# FFT_IFFT.net
KiCad netlist of a schematic drawn in Altium Designer
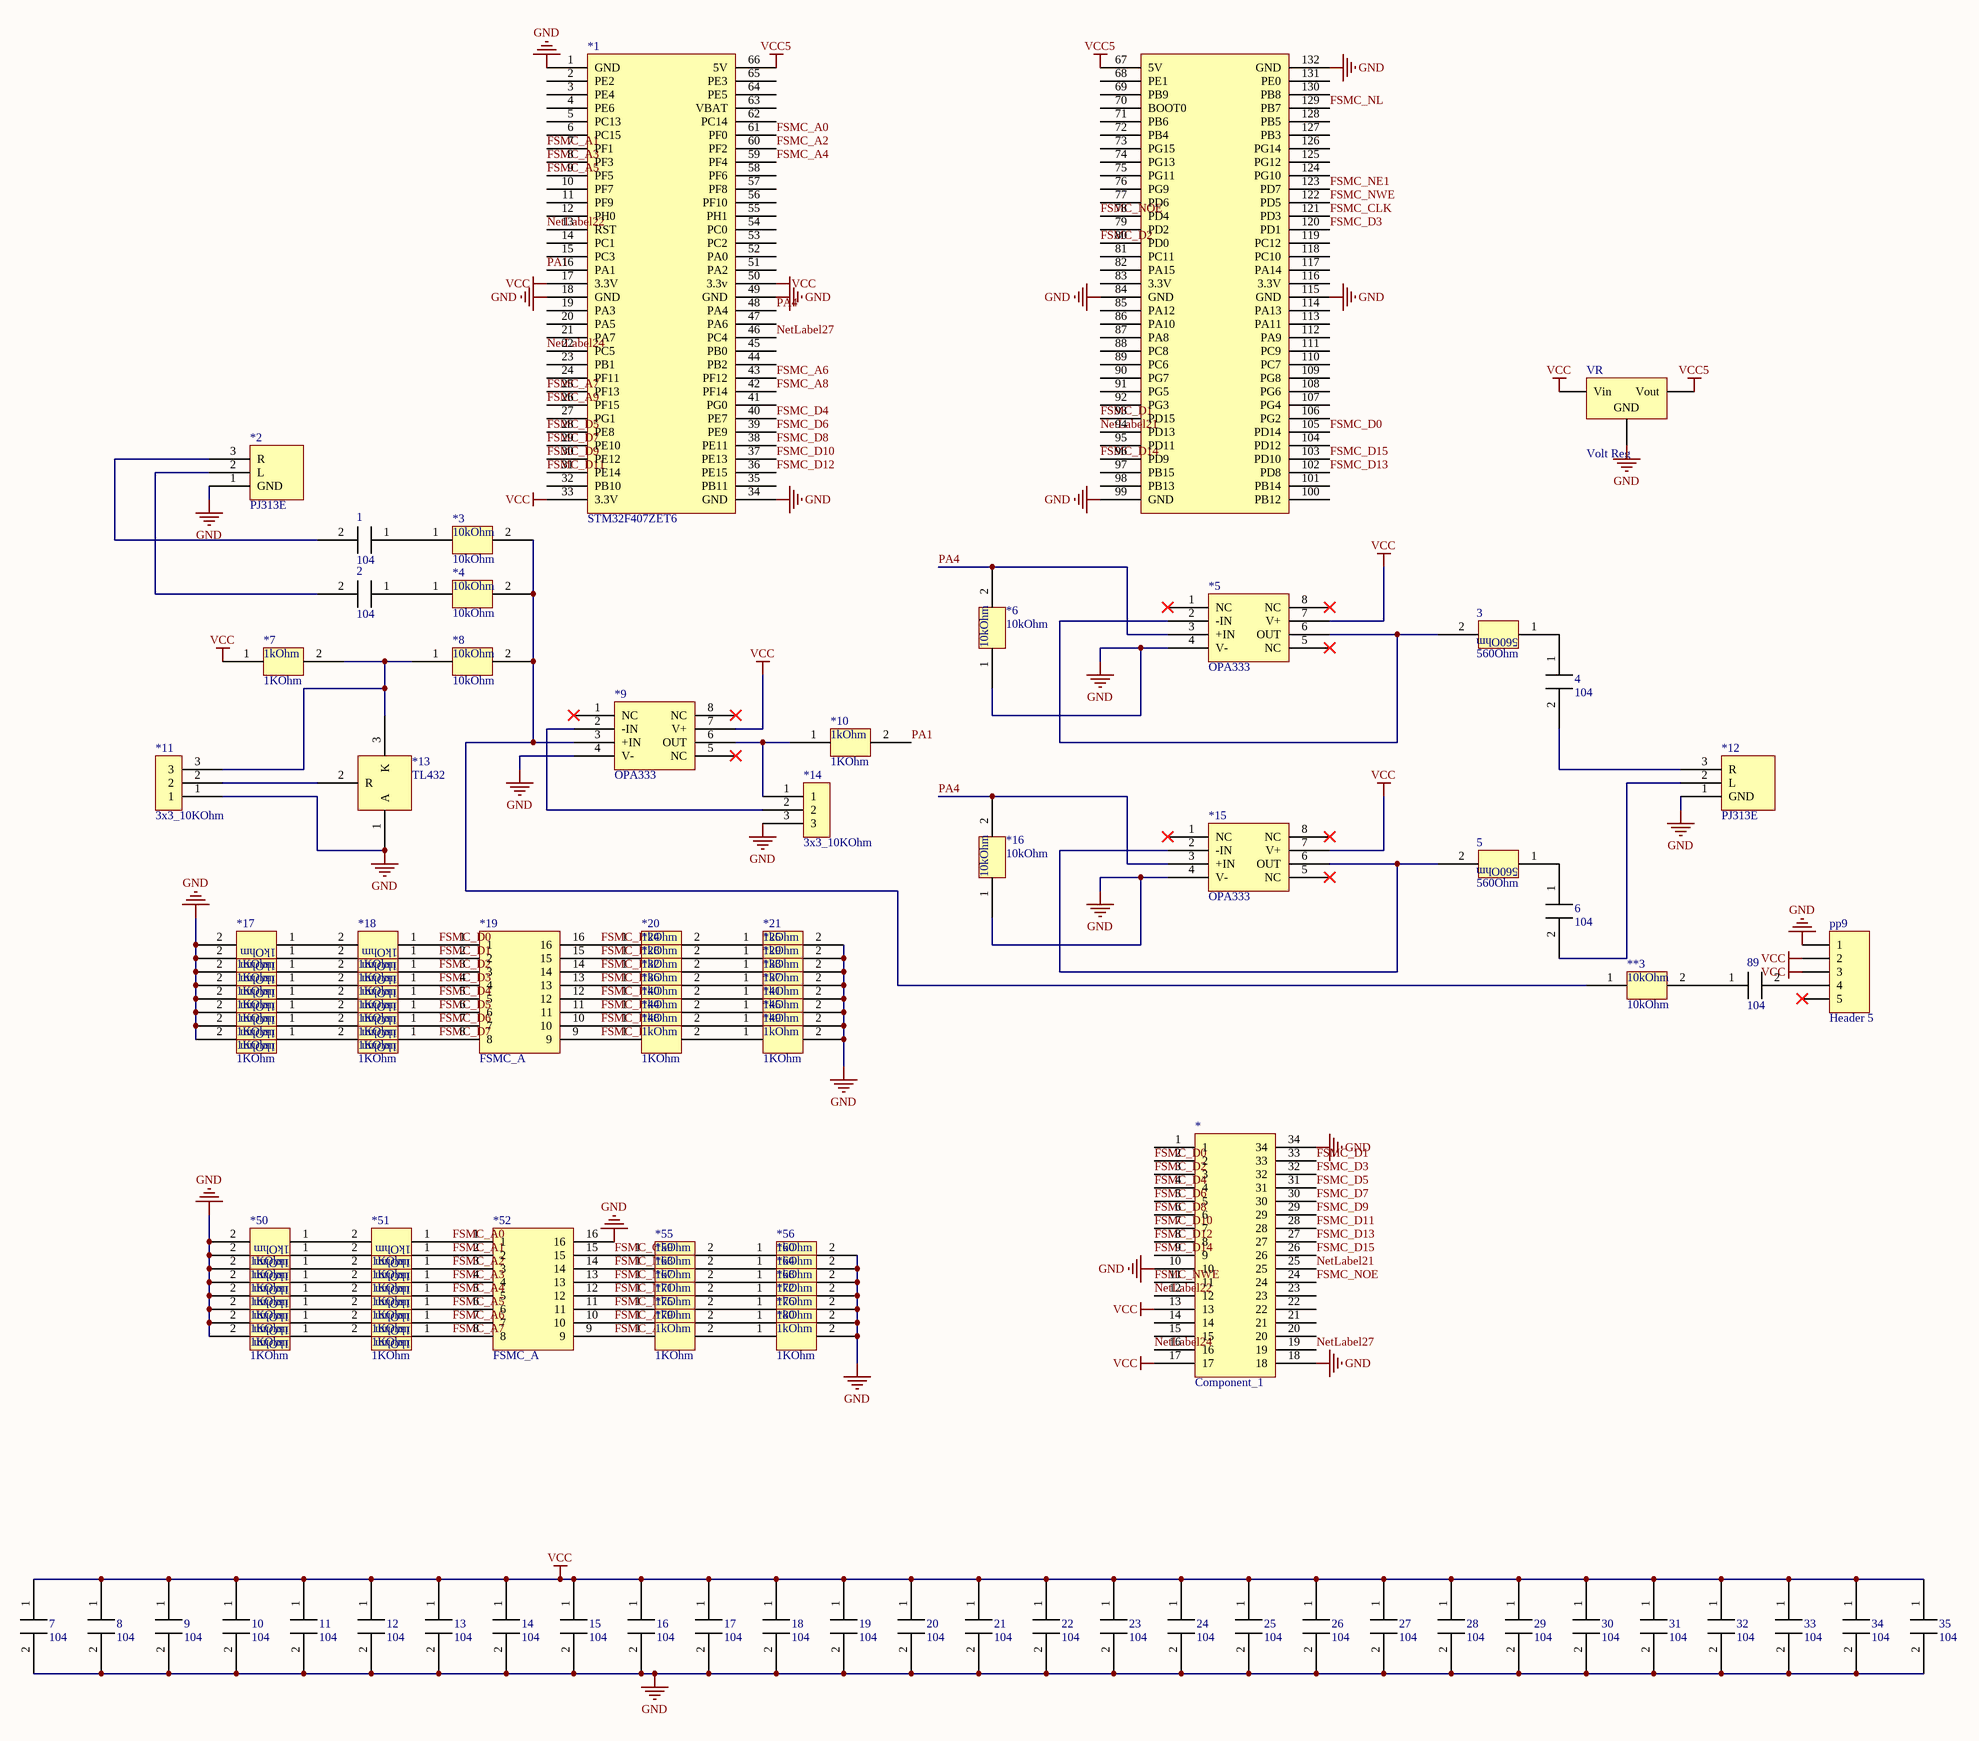
[diagram p0: FFT_IFFT.SchDoc]

(export (version "E")
  (design (tool "Eeschema 10.0.6"))
  (components
    (comp (ref "*")
      (value "Component_1")
      (footprint "PCBComponent_1")
      (libsource (lib "Schlib1") (part "Component_1"))
    )
    (comp (ref "**3") (value "10kOhm") (footprint "104") (libsource (lib "Schlib1") (part "10kOhm")))
    (comp (ref "*1")
      (value "STM32F407ZET6")
      (footprint "STM32F407ZET6")
      (libsource (lib "Schlib1") (part "STM32F407ZET6"))
    )
    (comp (ref "*2") (value "PJ313E") (footprint "PJ313E") (libsource (lib "Schlib1") (part "PJ313E")))
    (comp (ref "*3") (value "10kOhm") (footprint "104") (libsource (lib "Schlib1") (part "10kOhm")))
    (comp (ref "*4") (value "10kOhm") (footprint "104") (libsource (lib "Schlib1") (part "10kOhm")))
    (comp (ref "*5") (value "OPA333") (footprint "OPA333") (libsource (lib "Schlib1") (part "OPA333")))
    (comp (ref "*6") (value "10kOhm") (footprint "104") (libsource (lib "") (part "10kOhm_1")))
    (comp (ref "*7") (value "1KOhm") (footprint "104") (libsource (lib "") (part "1KOhm_1")))
    (comp (ref "*8") (value "10kOhm") (footprint "104") (libsource (lib "Schlib1") (part "10kOhm")))
    (comp (ref "*9") (value "OPA333") (footprint "OPA333") (libsource (lib "Schlib1") (part "OPA333")))
    (comp (ref "*10") (value "1KOhm") (footprint "104") (libsource (lib "") (part "1KOhm_1")))
    (comp (ref "*11")
      (value "3x3_10KOhm")
      (footprint "3x3_10KOhm")
      (libsource (lib "Schlib1") (part "3x3_10KOhm"))
    )
    (comp (ref "*12") (value "PJ313E") (footprint "PJ313E") (libsource (lib "Schlib1") (part "PJ313E")))
    (comp (ref "*13") (value "TL432") (footprint "AO3401") (libsource (lib "Schlib1") (part "TL432")))
    (comp (ref "*14")
      (value "3x3_10KOhm")
      (footprint "3x3_10KOhm")
      (libsource (lib "") (part "3x3_10KOhm_1"))
    )
    (comp (ref "*15") (value "OPA333") (footprint "OPA333") (libsource (lib "Schlib1") (part "OPA333")))
    (comp (ref "*16") (value "10kOhm") (footprint "104") (libsource (lib "") (part "10kOhm_1")))
    (comp (ref "*17") (value "1KOhm") (footprint "104") (libsource (lib "Schlib1") (part "1KOhm")))
    (comp (ref "*18") (value "1KOhm") (footprint "104") (libsource (lib "Schlib1") (part "1KOhm")))
    (comp (ref "*19") (value "FSMC_A") (footprint "DIP32") (libsource (lib "Schlib1") (part "FSMC_A")))
    (comp (ref "*20") (value "1KOhm") (footprint "104") (libsource (lib "") (part "1KOhm_1")))
    (comp (ref "*21") (value "1KOhm") (footprint "104") (libsource (lib "") (part "1KOhm_1")))
    (comp (ref "*22") (value "1KOhm") (footprint "104") (libsource (lib "Schlib1") (part "1KOhm")))
    (comp (ref "*23") (value "1KOhm") (footprint "104") (libsource (lib "Schlib1") (part "1KOhm")))
    (comp (ref "*24") (value "1KOhm") (footprint "104") (libsource (lib "") (part "1KOhm_1")))
    (comp (ref "*25") (value "1KOhm") (footprint "104") (libsource (lib "") (part "1KOhm_1")))
    (comp (ref "*26") (value "1KOhm") (footprint "104") (libsource (lib "Schlib1") (part "1KOhm")))
    (comp (ref "*27") (value "1KOhm") (footprint "104") (libsource (lib "Schlib1") (part "1KOhm")))
    (comp (ref "*28") (value "1KOhm") (footprint "104") (libsource (lib "") (part "1KOhm_1")))
    (comp (ref "*29") (value "1KOhm") (footprint "104") (libsource (lib "") (part "1KOhm_1")))
    (comp (ref "*30") (value "1KOhm") (footprint "104") (libsource (lib "Schlib1") (part "1KOhm")))
    (comp (ref "*31") (value "1KOhm") (footprint "104") (libsource (lib "Schlib1") (part "1KOhm")))
    (comp (ref "*32") (value "1KOhm") (footprint "104") (libsource (lib "") (part "1KOhm_1")))
    (comp (ref "*33") (value "1KOhm") (footprint "104") (libsource (lib "") (part "1KOhm_1")))
    (comp (ref "*34") (value "1KOhm") (footprint "104") (libsource (lib "Schlib1") (part "1KOhm")))
    (comp (ref "*35") (value "1KOhm") (footprint "104") (libsource (lib "Schlib1") (part "1KOhm")))
    (comp (ref "*36") (value "1KOhm") (footprint "104") (libsource (lib "") (part "1KOhm_1")))
    (comp (ref "*37") (value "1KOhm") (footprint "104") (libsource (lib "") (part "1KOhm_1")))
    (comp (ref "*38") (value "1KOhm") (footprint "104") (libsource (lib "Schlib1") (part "1KOhm")))
    (comp (ref "*39") (value "1KOhm") (footprint "104") (libsource (lib "Schlib1") (part "1KOhm")))
    (comp (ref "*40") (value "1KOhm") (footprint "104") (libsource (lib "") (part "1KOhm_1")))
    (comp (ref "*41") (value "1KOhm") (footprint "104") (libsource (lib "") (part "1KOhm_1")))
    (comp (ref "*42") (value "1KOhm") (footprint "104") (libsource (lib "Schlib1") (part "1KOhm")))
    (comp (ref "*43") (value "1KOhm") (footprint "104") (libsource (lib "Schlib1") (part "1KOhm")))
    (comp (ref "*44") (value "1KOhm") (footprint "104") (libsource (lib "") (part "1KOhm_1")))
    (comp (ref "*45") (value "1KOhm") (footprint "104") (libsource (lib "") (part "1KOhm_1")))
    (comp (ref "*46") (value "1KOhm") (footprint "104") (libsource (lib "Schlib1") (part "1KOhm")))
    (comp (ref "*47") (value "1KOhm") (footprint "104") (libsource (lib "Schlib1") (part "1KOhm")))
    (comp (ref "*48") (value "1KOhm") (footprint "104") (libsource (lib "") (part "1KOhm_1")))
    (comp (ref "*49") (value "1KOhm") (footprint "104") (libsource (lib "") (part "1KOhm_1")))
    (comp (ref "*50") (value "1KOhm") (footprint "104") (libsource (lib "Schlib1") (part "1KOhm")))
    (comp (ref "*51") (value "1KOhm") (footprint "104") (libsource (lib "Schlib1") (part "1KOhm")))
    (comp (ref "*52") (value "FSMC_A") (footprint "DIP32") (libsource (lib "Schlib1") (part "FSMC_A")))
    (comp (ref "*53") (value "1KOhm") (footprint "104") (libsource (lib "Schlib1") (part "1KOhm")))
    (comp (ref "*54") (value "1KOhm") (footprint "104") (libsource (lib "Schlib1") (part "1KOhm")))
    (comp (ref "*55") (value "1KOhm") (footprint "104") (libsource (lib "") (part "1KOhm_1")))
    (comp (ref "*56") (value "1KOhm") (footprint "104") (libsource (lib "") (part "1KOhm_1")))
    (comp (ref "*57") (value "1KOhm") (footprint "104") (libsource (lib "Schlib1") (part "1KOhm")))
    (comp (ref "*58") (value "1KOhm") (footprint "104") (libsource (lib "Schlib1") (part "1KOhm")))
    (comp (ref "*59") (value "1KOhm") (footprint "104") (libsource (lib "") (part "1KOhm_1")))
    (comp (ref "*60") (value "1KOhm") (footprint "104") (libsource (lib "") (part "1KOhm_1")))
    (comp (ref "*61") (value "1KOhm") (footprint "104") (libsource (lib "Schlib1") (part "1KOhm")))
    (comp (ref "*62") (value "1KOhm") (footprint "104") (libsource (lib "Schlib1") (part "1KOhm")))
    (comp (ref "*63") (value "1KOhm") (footprint "104") (libsource (lib "") (part "1KOhm_1")))
    (comp (ref "*64") (value "1KOhm") (footprint "104") (libsource (lib "") (part "1KOhm_1")))
    (comp (ref "*65") (value "1KOhm") (footprint "104") (libsource (lib "Schlib1") (part "1KOhm")))
    (comp (ref "*66") (value "1KOhm") (footprint "104") (libsource (lib "Schlib1") (part "1KOhm")))
    (comp (ref "*67") (value "1KOhm") (footprint "104") (libsource (lib "") (part "1KOhm_1")))
    (comp (ref "*68") (value "1KOhm") (footprint "104") (libsource (lib "") (part "1KOhm_1")))
    (comp (ref "*69") (value "1KOhm") (footprint "104") (libsource (lib "Schlib1") (part "1KOhm")))
    (comp (ref "*70") (value "1KOhm") (footprint "104") (libsource (lib "Schlib1") (part "1KOhm")))
    (comp (ref "*71") (value "1KOhm") (footprint "104") (libsource (lib "") (part "1KOhm_1")))
    (comp (ref "*72") (value "1KOhm") (footprint "104") (libsource (lib "") (part "1KOhm_1")))
    (comp (ref "*73") (value "1KOhm") (footprint "104") (libsource (lib "Schlib1") (part "1KOhm")))
    (comp (ref "*74") (value "1KOhm") (footprint "104") (libsource (lib "Schlib1") (part "1KOhm")))
    (comp (ref "*75") (value "1KOhm") (footprint "104") (libsource (lib "") (part "1KOhm_1")))
    (comp (ref "*76") (value "1KOhm") (footprint "104") (libsource (lib "") (part "1KOhm_1")))
    (comp (ref "*77") (value "1KOhm") (footprint "104") (libsource (lib "Schlib1") (part "1KOhm")))
    (comp (ref "*78") (value "1KOhm") (footprint "104") (libsource (lib "Schlib1") (part "1KOhm")))
    (comp (ref "*79") (value "1KOhm") (footprint "104") (libsource (lib "") (part "1KOhm_1")))
    (comp (ref "*80") (value "1KOhm") (footprint "104") (libsource (lib "") (part "1KOhm_1")))
    (comp (ref "1") (value "104") (footprint "104") (libsource (lib "Schlib1") (part "104")))
    (comp (ref "2") (value "104") (footprint "104") (libsource (lib "Schlib1") (part "104")))
    (comp (ref "3") (value "560Ohm") (footprint "104") (libsource (lib "Schlib1") (part "560Ohm")))
    (comp (ref "4") (value "104") (footprint "104") (libsource (lib "Schlib1") (part "104")))
    (comp (ref "5") (value "560Ohm") (footprint "104") (libsource (lib "Schlib1") (part "560Ohm")))
    (comp (ref "6") (value "104") (footprint "104") (libsource (lib "Schlib1") (part "104")))
    (comp (ref "7") (value "104") (footprint "104") (libsource (lib "Schlib1") (part "104")))
    (comp (ref "8") (value "104") (footprint "104") (libsource (lib "Schlib1") (part "104")))
    (comp (ref "9") (value "104") (footprint "104") (libsource (lib "Schlib1") (part "104")))
    (comp (ref "10") (value "104") (footprint "104") (libsource (lib "Schlib1") (part "104")))
    (comp (ref "11") (value "104") (footprint "104") (libsource (lib "Schlib1") (part "104")))
    (comp (ref "12") (value "104") (footprint "104") (libsource (lib "Schlib1") (part "104")))
    (comp (ref "13") (value "104") (footprint "104") (libsource (lib "Schlib1") (part "104")))
    (comp (ref "14") (value "104") (footprint "104") (libsource (lib "Schlib1") (part "104")))
    (comp (ref "15") (value "104") (footprint "104") (libsource (lib "Schlib1") (part "104")))
    (comp (ref "16") (value "104") (footprint "104") (libsource (lib "Schlib1") (part "104")))
    (comp (ref "17") (value "104") (footprint "104") (libsource (lib "Schlib1") (part "104")))
    (comp (ref "18") (value "104") (footprint "104") (libsource (lib "Schlib1") (part "104")))
    (comp (ref "19") (value "104") (footprint "104") (libsource (lib "Schlib1") (part "104")))
    (comp (ref "20") (value "104") (footprint "104") (libsource (lib "Schlib1") (part "104")))
    (comp (ref "21") (value "104") (footprint "104") (libsource (lib "Schlib1") (part "104")))
    (comp (ref "22") (value "104") (footprint "104") (libsource (lib "Schlib1") (part "104")))
    (comp (ref "23") (value "104") (footprint "104") (libsource (lib "Schlib1") (part "104")))
    (comp (ref "24") (value "104") (footprint "104") (libsource (lib "Schlib1") (part "104")))
    (comp (ref "25") (value "104") (footprint "104") (libsource (lib "Schlib1") (part "104")))
    (comp (ref "26") (value "104") (footprint "104") (libsource (lib "Schlib1") (part "104")))
    (comp (ref "27") (value "104") (footprint "104") (libsource (lib "Schlib1") (part "104")))
    (comp (ref "28") (value "104") (footprint "104") (libsource (lib "Schlib1") (part "104")))
    (comp (ref "29") (value "104") (footprint "104") (libsource (lib "Schlib1") (part "104")))
    (comp (ref "30") (value "104") (footprint "104") (libsource (lib "Schlib1") (part "104")))
    (comp (ref "31") (value "104") (footprint "104") (libsource (lib "Schlib1") (part "104")))
    (comp (ref "32") (value "104") (footprint "104") (libsource (lib "Schlib1") (part "104")))
    (comp (ref "33") (value "104") (footprint "104") (libsource (lib "Schlib1") (part "104")))
    (comp (ref "34") (value "104") (footprint "104") (libsource (lib "Schlib1") (part "104")))
    (comp (ref "35") (value "104") (footprint "104") (libsource (lib "Schlib1") (part "104")))
    (comp (ref "89") (value "104") (footprint "104") (libsource (lib "Schlib1") (part "104")))
    (comp (ref "pp9")
      (value "Header 5")
      (footprint "HDR1X5")
      (description "Header, 5-Pin")
      (fields (field (name "PUBLISHER") "Altium Limited"))
      (libsource (lib "Miscellaneous Connectors") (part "Header 5"))
    )
    (comp (ref "VR")
      (value "Volt Reg")
      (footprint "TO252")
      (description "Voltage Regulator")
      (fields (field (name "PUBLISHER") "Altium Limited"))
      (libsource (lib "Miscellaneous Devices") (part "Volt Reg"))
    )
  )
  (nets
    (net (code "1") (name "/FSMC_A0") (class "Default")
      (node (ref "*1") (pin "61") (pinfunction "PF0_61") (pintype "passive"))
      (node (ref "*51") (pin "1") (pintype "passive"))
      (node (ref "*52") (pin "1") (pinfunction "1_1") (pintype "passive"))
    )
    (net (code "2") (name "/FSMC_A1") (class "Default")
      (node (ref "*1") (pin "7") (pinfunction "PF1_7") (pintype "passive"))
      (node (ref "*52") (pin "2") (pinfunction "2_2") (pintype "passive"))
      (node (ref "*54") (pin "1") (pintype "passive"))
    )
    (net (code "3") (name "/FSMC_A2") (class "Default")
      (node (ref "*1") (pin "60") (pinfunction "PF2_60") (pintype "passive"))
      (node (ref "*52") (pin "3") (pinfunction "3_3") (pintype "passive"))
      (node (ref "*58") (pin "1") (pintype "passive"))
    )
    (net (code "4") (name "/FSMC_A3") (class "Default")
      (node (ref "*1") (pin "8") (pinfunction "PF3_8") (pintype "passive"))
      (node (ref "*52") (pin "4") (pinfunction "4_4") (pintype "passive"))
      (node (ref "*62") (pin "1") (pintype "passive"))
    )
    (net (code "5") (name "/FSMC_A4") (class "Default")
      (node (ref "*1") (pin "59") (pinfunction "PF4_59") (pintype "passive"))
      (node (ref "*52") (pin "5") (pinfunction "5_5") (pintype "passive"))
      (node (ref "*66") (pin "1") (pintype "passive"))
    )
    (net (code "6") (name "/FSMC_A5") (class "Default")
      (node (ref "*1") (pin "9") (pinfunction "PF5_9") (pintype "passive"))
      (node (ref "*52") (pin "6") (pinfunction "6_6") (pintype "passive"))
      (node (ref "*70") (pin "1") (pintype "passive"))
    )
    (net (code "7") (name "/FSMC_A6") (class "Default")
      (node (ref "*1") (pin "43") (pinfunction "PF12_43") (pintype "passive"))
      (node (ref "*52") (pin "7") (pinfunction "7_7") (pintype "passive"))
      (node (ref "*74") (pin "1") (pintype "passive"))
    )
    (net (code "8") (name "/FSMC_A7") (class "Default")
      (node (ref "*1") (pin "25") (pinfunction "PF13_25") (pintype "passive"))
      (node (ref "*52") (pin "8") (pinfunction "8_8") (pintype "passive"))
      (node (ref "*78") (pin "1") (pintype "passive"))
    )
    (net (code "9") (name "/FSMC_A8") (class "Default")
      (node (ref "*1") (pin "42") (pinfunction "PF14_42") (pintype "passive"))
      (node (ref "*52") (pin "9") (pinfunction "9_9") (pintype "passive"))
      (node (ref "*79") (pin "1") (pintype "passive"))
    )
    (net (code "10") (name "/FSMC_A9") (class "Default")
      (node (ref "*1") (pin "26") (pinfunction "PF15_26") (pintype "passive"))
      (node (ref "*52") (pin "10") (pinfunction "10_10") (pintype "passive"))
      (node (ref "*75") (pin "1") (pintype "passive"))
    )
    (net (code "11") (name "/FSMC_CLK") (class "Default")
      (node (ref "*1") (pin "121") (pinfunction "PD3_121") (pintype "passive"))
      (node (ref "*52") (pin "15") (pinfunction "15_15") (pintype "passive"))
      (node (ref "*55") (pin "1") (pintype "passive"))
    )
    (net (code "12") (name "/FSMC_D0") (class "Default")
      (node (ref "*") (pin "2") (pinfunction "2_2") (pintype "passive"))
      (node (ref "*1") (pin "105") (pinfunction "PD14_105") (pintype "passive"))
      (node (ref "*18") (pin "1") (pintype "passive"))
      (node (ref "*19") (pin "1") (pinfunction "1_1") (pintype "passive"))
    )
    (net (code "13") (name "/FSMC_D1") (class "Default")
      (node (ref "*") (pin "33") (pinfunction "33_33") (pintype "passive"))
      (node (ref "*1") (pin "93") (pinfunction "PD15_93") (pintype "passive"))
      (node (ref "*19") (pin "2") (pinfunction "2_2") (pintype "passive"))
      (node (ref "*23") (pin "1") (pintype "passive"))
    )
    (net (code "14") (name "/FSMC_D2") (class "Default")
      (node (ref "*") (pin "3") (pinfunction "3_3") (pintype "passive"))
      (node (ref "*1") (pin "80") (pinfunction "PD0_80") (pintype "passive"))
      (node (ref "*19") (pin "3") (pinfunction "3_3") (pintype "passive"))
      (node (ref "*27") (pin "1") (pintype "passive"))
    )
    (net (code "15") (name "/FSMC_D3") (class "Default")
      (node (ref "*") (pin "32") (pinfunction "32_32") (pintype "passive"))
      (node (ref "*1") (pin "120") (pinfunction "PD1_120") (pintype "passive"))
      (node (ref "*19") (pin "4") (pinfunction "4_4") (pintype "passive"))
      (node (ref "*31") (pin "1") (pintype "passive"))
    )
    (net (code "16") (name "/FSMC_D4") (class "Default")
      (node (ref "*") (pin "4") (pinfunction "4_4") (pintype "passive"))
      (node (ref "*1") (pin "40") (pinfunction "PE7_40") (pintype "passive"))
      (node (ref "*19") (pin "5") (pinfunction "5_5") (pintype "passive"))
      (node (ref "*35") (pin "1") (pintype "passive"))
    )
    (net (code "17") (name "/FSMC_D5") (class "Default")
      (node (ref "*") (pin "31") (pinfunction "31_31") (pintype "passive"))
      (node (ref "*1") (pin "28") (pinfunction "PE8_28") (pintype "passive"))
      (node (ref "*19") (pin "6") (pinfunction "6_6") (pintype "passive"))
      (node (ref "*39") (pin "1") (pintype "passive"))
    )
    (net (code "18") (name "/FSMC_D6") (class "Default")
      (node (ref "*") (pin "5") (pinfunction "5_5") (pintype "passive"))
      (node (ref "*1") (pin "39") (pinfunction "PE9_39") (pintype "passive"))
      (node (ref "*19") (pin "7") (pinfunction "7_7") (pintype "passive"))
      (node (ref "*43") (pin "1") (pintype "passive"))
    )
    (net (code "19") (name "/FSMC_D7") (class "Default")
      (node (ref "*") (pin "30") (pinfunction "30_30") (pintype "passive"))
      (node (ref "*1") (pin "29") (pinfunction "PE10_29") (pintype "passive"))
      (node (ref "*19") (pin "8") (pinfunction "8_8") (pintype "passive"))
      (node (ref "*47") (pin "1") (pintype "passive"))
    )
    (net (code "20") (name "/FSMC_D8") (class "Default")
      (node (ref "*") (pin "6") (pinfunction "6_6") (pintype "passive"))
      (node (ref "*1") (pin "38") (pinfunction "PE11_38") (pintype "passive"))
      (node (ref "*19") (pin "9") (pinfunction "9_9") (pintype "passive"))
      (node (ref "*48") (pin "1") (pintype "passive"))
    )
    (net (code "21") (name "/FSMC_D9") (class "Default")
      (node (ref "*") (pin "29") (pinfunction "29_29") (pintype "passive"))
      (node (ref "*1") (pin "30") (pinfunction "PE12_30") (pintype "passive"))
      (node (ref "*19") (pin "10") (pinfunction "10_10") (pintype "passive"))
      (node (ref "*44") (pin "1") (pintype "passive"))
    )
    (net (code "22") (name "/FSMC_D10") (class "Default")
      (node (ref "*") (pin "7") (pinfunction "7_7") (pintype "passive"))
      (node (ref "*1") (pin "37") (pinfunction "PE13_37") (pintype "passive"))
      (node (ref "*19") (pin "11") (pinfunction "11_11") (pintype "passive"))
      (node (ref "*40") (pin "1") (pintype "passive"))
    )
    (net (code "23") (name "/FSMC_D11") (class "Default")
      (node (ref "*") (pin "28") (pinfunction "28_28") (pintype "passive"))
      (node (ref "*1") (pin "31") (pinfunction "PE14_31") (pintype "passive"))
      (node (ref "*19") (pin "12") (pinfunction "12_12") (pintype "passive"))
      (node (ref "*36") (pin "1") (pintype "passive"))
    )
    (net (code "24") (name "/FSMC_D12") (class "Default")
      (node (ref "*") (pin "8") (pinfunction "8_8") (pintype "passive"))
      (node (ref "*1") (pin "36") (pinfunction "PE15_36") (pintype "passive"))
      (node (ref "*19") (pin "13") (pinfunction "13_13") (pintype "passive"))
      (node (ref "*32") (pin "1") (pintype "passive"))
    )
    (net (code "25") (name "/FSMC_D13") (class "Default")
      (node (ref "*") (pin "27") (pinfunction "27_27") (pintype "passive"))
      (node (ref "*1") (pin "102") (pinfunction "PD8_102") (pintype "passive"))
      (node (ref "*19") (pin "14") (pinfunction "14_14") (pintype "passive"))
      (node (ref "*28") (pin "1") (pintype "passive"))
    )
    (net (code "26") (name "/FSMC_D14") (class "Default")
      (node (ref "*") (pin "9") (pinfunction "9_9") (pintype "passive"))
      (node (ref "*1") (pin "96") (pinfunction "PD9_96") (pintype "passive"))
      (node (ref "*19") (pin "15") (pinfunction "15_15") (pintype "passive"))
      (node (ref "*24") (pin "1") (pintype "passive"))
    )
    (net (code "27") (name "/FSMC_D15") (class "Default")
      (node (ref "*") (pin "26") (pinfunction "26_26") (pintype "passive"))
      (node (ref "*1") (pin "103") (pinfunction "PD10_103") (pintype "passive"))
      (node (ref "*19") (pin "16") (pinfunction "16_16") (pintype "passive"))
      (node (ref "*20") (pin "1") (pintype "passive"))
    )
    (net (code "28") (name "/FSMC_NE1") (class "Default")
      (node (ref "*1") (pin "123") (pinfunction "PD7_123") (pintype "passive"))
      (node (ref "*52") (pin "12") (pinfunction "12_12") (pintype "passive"))
      (node (ref "*67") (pin "1") (pintype "passive"))
    )
    (net (code "29") (name "/FSMC_NL") (class "Default")
      (node (ref "*1") (pin "129") (pinfunction "PB7_129") (pintype "passive"))
      (node (ref "*52") (pin "11") (pinfunction "11_11") (pintype "passive"))
      (node (ref "*71") (pin "1") (pintype "passive"))
    )
    (net (code "30") (name "/FSMC_NOE") (class "Default")
      (node (ref "*") (pin "24") (pinfunction "24_24") (pintype "passive"))
      (node (ref "*1") (pin "78") (pinfunction "PD4_78") (pintype "passive"))
      (node (ref "*52") (pin "14") (pinfunction "14_14") (pintype "passive"))
      (node (ref "*59") (pin "1") (pintype "passive"))
    )
    (net (code "31") (name "/FSMC_NWE") (class "Default")
      (node (ref "*") (pin "11") (pinfunction "11_11") (pintype "passive"))
      (node (ref "*1") (pin "122") (pinfunction "PD5_122") (pintype "passive"))
      (node (ref "*52") (pin "13") (pinfunction "13_13") (pintype "passive"))
      (node (ref "*63") (pin "1") (pintype "passive"))
    )
    (net (code "32") (name "/NetLabel21") (class "Default")
      (node (ref "*") (pin "25") (pinfunction "25_25") (pintype "passive"))
      (node (ref "*1") (pin "94") (pinfunction "PD13_94") (pintype "passive"))
    )
    (net (code "33") (name "/NetLabel22") (class "Default")
      (node (ref "*") (pin "12") (pinfunction "12_12") (pintype "passive"))
      (node (ref "*1") (pin "13") (pinfunction "RST_13") (pintype "passive"))
    )
    (net (code "34") (name "/NetLabel24") (class "Default")
      (node (ref "*") (pin "16") (pinfunction "16_16") (pintype "passive"))
      (node (ref "*1") (pin "22") (pinfunction "PC5_22") (pintype "passive"))
    )
    (net (code "35") (name "/NetLabel27") (class "Default")
      (node (ref "*") (pin "19") (pinfunction "19_19") (pintype "passive"))
      (node (ref "*1") (pin "46") (pinfunction "PC4_46") (pintype "passive"))
    )
    (net (code "36") (name "/PA1") (class "Default")
      (node (ref "*1") (pin "16") (pinfunction "PA1_16") (pintype "passive"))
      (node (ref "*10") (pin "2") (pintype "passive"))
    )
    (net (code "37") (name "/PA4") (class "Default")
      (node (ref "*1") (pin "48") (pinfunction "PA4_48") (pintype "passive"))
      (node (ref "*15") (pin "3") (pinfunction "+IN_3") (pintype "passive"))
      (node (ref "*16") (pin "2") (pintype "passive"))
      (node (ref "*5") (pin "3") (pinfunction "+IN_3") (pintype "passive"))
      (node (ref "*6") (pin "2") (pintype "passive"))
    )
    (net (code "38") (name "GND") (class "Default")
      (node (ref "*") (pin "10") (pinfunction "10_10") (pintype "passive"))
      (node (ref "*") (pin "18") (pinfunction "18_18") (pintype "passive"))
      (node (ref "*") (pin "34") (pinfunction "34_34") (pintype "passive"))
      (node (ref "*1") (pin "1") (pinfunction "GND_1") (pintype "passive"))
      (node (ref "*1") (pin "115") (pinfunction "GND_115") (pintype "passive"))
      (node (ref "*1") (pin "132") (pinfunction "GND_132") (pintype "passive"))
      (node (ref "*1") (pin "18") (pinfunction "GND_18") (pintype "passive"))
      (node (ref "*1") (pin "34") (pinfunction "GND_34") (pintype "passive"))
      (node (ref "*1") (pin "49") (pinfunction "GND_49") (pintype "passive"))
      (node (ref "*1") (pin "84") (pinfunction "GND_84") (pintype "passive"))
      (node (ref "*1") (pin "99") (pinfunction "GND_99") (pintype "passive"))
      (node (ref "*11") (pin "1") (pinfunction "1_1") (pintype "passive"))
      (node (ref "*12") (pin "1") (pinfunction "GND_1") (pintype "passive"))
      (node (ref "*13") (pin "1") (pinfunction "A_1") (pintype "passive"))
      (node (ref "*14") (pin "3") (pinfunction "3_3") (pintype "passive"))
      (node (ref "*15") (pin "4") (pinfunction "V-_4") (pintype "passive"))
      (node (ref "*16") (pin "1") (pintype "passive"))
      (node (ref "*17") (pin "2") (pintype "passive"))
      (node (ref "*2") (pin "1") (pinfunction "GND_1") (pintype "passive"))
      (node (ref "*21") (pin "2") (pintype "passive"))
      (node (ref "*22") (pin "2") (pintype "passive"))
      (node (ref "*25") (pin "2") (pintype "passive"))
      (node (ref "*26") (pin "2") (pintype "passive"))
      (node (ref "*29") (pin "2") (pintype "passive"))
      (node (ref "*30") (pin "2") (pintype "passive"))
      (node (ref "*33") (pin "2") (pintype "passive"))
      (node (ref "*34") (pin "2") (pintype "passive"))
      (node (ref "*37") (pin "2") (pintype "passive"))
      (node (ref "*38") (pin "2") (pintype "passive"))
      (node (ref "*41") (pin "2") (pintype "passive"))
      (node (ref "*42") (pin "2") (pintype "passive"))
      (node (ref "*45") (pin "2") (pintype "passive"))
      (node (ref "*46") (pin "2") (pintype "passive"))
      (node (ref "*49") (pin "2") (pintype "passive"))
      (node (ref "*5") (pin "4") (pinfunction "V-_4") (pintype "passive"))
      (node (ref "*50") (pin "2") (pintype "passive"))
      (node (ref "*52") (pin "16") (pinfunction "16_16") (pintype "passive"))
      (node (ref "*53") (pin "2") (pintype "passive"))
      (node (ref "*56") (pin "2") (pintype "passive"))
      (node (ref "*57") (pin "2") (pintype "passive"))
      (node (ref "*6") (pin "1") (pintype "passive"))
      (node (ref "*60") (pin "2") (pintype "passive"))
      (node (ref "*61") (pin "2") (pintype "passive"))
      (node (ref "*64") (pin "2") (pintype "passive"))
      (node (ref "*65") (pin "2") (pintype "passive"))
      (node (ref "*68") (pin "2") (pintype "passive"))
      (node (ref "*69") (pin "2") (pintype "passive"))
      (node (ref "*72") (pin "2") (pintype "passive"))
      (node (ref "*73") (pin "2") (pintype "passive"))
      (node (ref "*76") (pin "2") (pintype "passive"))
      (node (ref "*77") (pin "2") (pintype "passive"))
      (node (ref "*80") (pin "2") (pintype "passive"))
      (node (ref "*9") (pin "4") (pinfunction "V-_4") (pintype "passive"))
      (node (ref "10") (pin "2") (pintype "passive"))
      (node (ref "11") (pin "2") (pintype "passive"))
      (node (ref "12") (pin "2") (pintype "passive"))
      (node (ref "13") (pin "2") (pintype "passive"))
      (node (ref "14") (pin "2") (pintype "passive"))
      (node (ref "15") (pin "2") (pintype "passive"))
      (node (ref "16") (pin "2") (pintype "passive"))
      (node (ref "17") (pin "2") (pintype "passive"))
      (node (ref "18") (pin "2") (pintype "passive"))
      (node (ref "19") (pin "2") (pintype "passive"))
      (node (ref "20") (pin "2") (pintype "passive"))
      (node (ref "21") (pin "2") (pintype "passive"))
      (node (ref "22") (pin "2") (pintype "passive"))
      (node (ref "23") (pin "2") (pintype "passive"))
      (node (ref "24") (pin "2") (pintype "passive"))
      (node (ref "25") (pin "2") (pintype "passive"))
      (node (ref "26") (pin "2") (pintype "passive"))
      (node (ref "27") (pin "2") (pintype "passive"))
      (node (ref "28") (pin "2") (pintype "passive"))
      (node (ref "29") (pin "2") (pintype "passive"))
      (node (ref "30") (pin "2") (pintype "passive"))
      (node (ref "31") (pin "2") (pintype "passive"))
      (node (ref "32") (pin "2") (pintype "passive"))
      (node (ref "33") (pin "2") (pintype "passive"))
      (node (ref "34") (pin "2") (pintype "passive"))
      (node (ref "35") (pin "2") (pintype "passive"))
      (node (ref "7") (pin "2") (pintype "passive"))
      (node (ref "8") (pin "2") (pintype "passive"))
      (node (ref "9") (pin "2") (pintype "passive"))
      (node (ref "VR") (pin "2") (pinfunction "GND_2") (pintype "passive"))
      (node (ref "pp9") (pin "1") (pinfunction "1_1") (pintype "passive"))
    )
    (net (code "39") (name "Net-(**3-Pad2)") (class "Default")
      (node (ref "**3") (pin "2") (pintype "passive"))
      (node (ref "89") (pin "1") (pintype "passive"))
    )
    (net (code "40") (name "Net-(*2-L)") (class "Default")
      (node (ref "*2") (pin "2") (pinfunction "L_2") (pintype "passive"))
      (node (ref "2") (pin "2") (pintype "passive"))
    )
    (net (code "41") (name "Net-(*2-R)") (class "Default")
      (node (ref "*2") (pin "3") (pinfunction "R_3") (pintype "passive"))
      (node (ref "1") (pin "2") (pintype "passive"))
    )
    (net (code "42") (name "Net-(*3-Pad1)") (class "Default")
      (node (ref "*3") (pin "1") (pintype "passive"))
      (node (ref "1") (pin "1") (pintype "passive"))
    )
    (net (code "43") (name "Net-(*4-Pad1)") (class "Default")
      (node (ref "*4") (pin "1") (pintype "passive"))
      (node (ref "2") (pin "1") (pintype "passive"))
    )
    (net (code "44") (name "Net-(*5--IN)") (class "Default")
      (node (ref "*5") (pin "2") (pinfunction "-IN_2") (pintype "passive"))
      (node (ref "*5") (pin "6") (pinfunction "OUT_6") (pintype "passive"))
      (node (ref "3") (pin "2") (pintype "passive"))
    )
    (net (code "45") (name "Net-(*9-+IN)") (class "Default")
      (node (ref "**3") (pin "1") (pintype "passive"))
      (node (ref "*3") (pin "2") (pintype "passive"))
      (node (ref "*4") (pin "2") (pintype "passive"))
      (node (ref "*8") (pin "2") (pintype "passive"))
      (node (ref "*9") (pin "3") (pinfunction "+IN_3") (pintype "passive"))
    )
    (net (code "46") (name "Net-(*9--IN)") (class "Default")
      (node (ref "*14") (pin "2") (pinfunction "2_2") (pintype "passive"))
      (node (ref "*9") (pin "2") (pinfunction "-IN_2") (pintype "passive"))
    )
    (net (code "47") (name "Net-(*9-OUT)") (class "Default")
      (node (ref "*10") (pin "1") (pintype "passive"))
      (node (ref "*14") (pin "1") (pinfunction "1_1") (pintype "passive"))
      (node (ref "*9") (pin "6") (pinfunction "OUT_6") (pintype "passive"))
    )
    (net (code "48") (name "Net-(*12-L)") (class "Default")
      (node (ref "*12") (pin "2") (pinfunction "L_2") (pintype "passive"))
      (node (ref "6") (pin "2") (pintype "passive"))
    )
    (net (code "49") (name "Net-(*12-R)") (class "Default")
      (node (ref "*12") (pin "3") (pinfunction "R_3") (pintype "passive"))
      (node (ref "4") (pin "2") (pintype "passive"))
    )
    (net (code "50") (name "Net-(*13-K)") (class "Default")
      (node (ref "*11") (pin "3") (pinfunction "3_3") (pintype "passive"))
      (node (ref "*13") (pin "3") (pinfunction "K_3") (pintype "passive"))
      (node (ref "*7") (pin "2") (pintype "passive"))
      (node (ref "*8") (pin "1") (pintype "passive"))
    )
    (net (code "51") (name "Net-(*13-R)") (class "Default")
      (node (ref "*11") (pin "2") (pinfunction "2_2") (pintype "passive"))
      (node (ref "*13") (pin "2") (pinfunction "R_2") (pintype "passive"))
    )
    (net (code "52") (name "Net-(*15--IN)") (class "Default")
      (node (ref "*15") (pin "2") (pinfunction "-IN_2") (pintype "passive"))
      (node (ref "*15") (pin "6") (pinfunction "OUT_6") (pintype "passive"))
      (node (ref "5") (pin "2") (pintype "passive"))
    )
    (net (code "53") (name "Net-(*17-Pad1)") (class "Default")
      (node (ref "*17") (pin "1") (pintype "passive"))
      (node (ref "*18") (pin "2") (pintype "passive"))
    )
    (net (code "54") (name "Net-(*20-Pad2)") (class "Default")
      (node (ref "*20") (pin "2") (pintype "passive"))
      (node (ref "*21") (pin "1") (pintype "passive"))
    )
    (net (code "55") (name "Net-(*22-Pad1)") (class "Default")
      (node (ref "*22") (pin "1") (pintype "passive"))
      (node (ref "*23") (pin "2") (pintype "passive"))
    )
    (net (code "56") (name "Net-(*24-Pad2)") (class "Default")
      (node (ref "*24") (pin "2") (pintype "passive"))
      (node (ref "*25") (pin "1") (pintype "passive"))
    )
    (net (code "57") (name "Net-(*26-Pad1)") (class "Default")
      (node (ref "*26") (pin "1") (pintype "passive"))
      (node (ref "*27") (pin "2") (pintype "passive"))
    )
    (net (code "58") (name "Net-(*28-Pad2)") (class "Default")
      (node (ref "*28") (pin "2") (pintype "passive"))
      (node (ref "*29") (pin "1") (pintype "passive"))
    )
    (net (code "59") (name "Net-(*30-Pad1)") (class "Default")
      (node (ref "*30") (pin "1") (pintype "passive"))
      (node (ref "*31") (pin "2") (pintype "passive"))
    )
    (net (code "60") (name "Net-(*32-Pad2)") (class "Default")
      (node (ref "*32") (pin "2") (pintype "passive"))
      (node (ref "*33") (pin "1") (pintype "passive"))
    )
    (net (code "61") (name "Net-(*34-Pad1)") (class "Default")
      (node (ref "*34") (pin "1") (pintype "passive"))
      (node (ref "*35") (pin "2") (pintype "passive"))
    )
    (net (code "62") (name "Net-(*36-Pad2)") (class "Default")
      (node (ref "*36") (pin "2") (pintype "passive"))
      (node (ref "*37") (pin "1") (pintype "passive"))
    )
    (net (code "63") (name "Net-(*38-Pad1)") (class "Default")
      (node (ref "*38") (pin "1") (pintype "passive"))
      (node (ref "*39") (pin "2") (pintype "passive"))
    )
    (net (code "64") (name "Net-(*40-Pad2)") (class "Default")
      (node (ref "*40") (pin "2") (pintype "passive"))
      (node (ref "*41") (pin "1") (pintype "passive"))
    )
    (net (code "65") (name "Net-(*42-Pad1)") (class "Default")
      (node (ref "*42") (pin "1") (pintype "passive"))
      (node (ref "*43") (pin "2") (pintype "passive"))
    )
    (net (code "66") (name "Net-(*44-Pad2)") (class "Default")
      (node (ref "*44") (pin "2") (pintype "passive"))
      (node (ref "*45") (pin "1") (pintype "passive"))
    )
    (net (code "67") (name "Net-(*46-Pad1)") (class "Default")
      (node (ref "*46") (pin "1") (pintype "passive"))
      (node (ref "*47") (pin "2") (pintype "passive"))
    )
    (net (code "68") (name "Net-(*48-Pad2)") (class "Default")
      (node (ref "*48") (pin "2") (pintype "passive"))
      (node (ref "*49") (pin "1") (pintype "passive"))
    )
    (net (code "69") (name "Net-(*50-Pad1)") (class "Default")
      (node (ref "*50") (pin "1") (pintype "passive"))
      (node (ref "*51") (pin "2") (pintype "passive"))
    )
    (net (code "70") (name "Net-(*53-Pad1)") (class "Default")
      (node (ref "*53") (pin "1") (pintype "passive"))
      (node (ref "*54") (pin "2") (pintype "passive"))
    )
    (net (code "71") (name "Net-(*55-Pad2)") (class "Default")
      (node (ref "*55") (pin "2") (pintype "passive"))
      (node (ref "*56") (pin "1") (pintype "passive"))
    )
    (net (code "72") (name "Net-(*57-Pad1)") (class "Default")
      (node (ref "*57") (pin "1") (pintype "passive"))
      (node (ref "*58") (pin "2") (pintype "passive"))
    )
    (net (code "73") (name "Net-(*59-Pad2)") (class "Default")
      (node (ref "*59") (pin "2") (pintype "passive"))
      (node (ref "*60") (pin "1") (pintype "passive"))
    )
    (net (code "74") (name "Net-(*61-Pad1)") (class "Default")
      (node (ref "*61") (pin "1") (pintype "passive"))
      (node (ref "*62") (pin "2") (pintype "passive"))
    )
    (net (code "75") (name "Net-(*63-Pad2)") (class "Default")
      (node (ref "*63") (pin "2") (pintype "passive"))
      (node (ref "*64") (pin "1") (pintype "passive"))
    )
    (net (code "76") (name "Net-(*65-Pad1)") (class "Default")
      (node (ref "*65") (pin "1") (pintype "passive"))
      (node (ref "*66") (pin "2") (pintype "passive"))
    )
    (net (code "77") (name "Net-(*67-Pad2)") (class "Default")
      (node (ref "*67") (pin "2") (pintype "passive"))
      (node (ref "*68") (pin "1") (pintype "passive"))
    )
    (net (code "78") (name "Net-(*69-Pad1)") (class "Default")
      (node (ref "*69") (pin "1") (pintype "passive"))
      (node (ref "*70") (pin "2") (pintype "passive"))
    )
    (net (code "79") (name "Net-(*71-Pad2)") (class "Default")
      (node (ref "*71") (pin "2") (pintype "passive"))
      (node (ref "*72") (pin "1") (pintype "passive"))
    )
    (net (code "80") (name "Net-(*73-Pad1)") (class "Default")
      (node (ref "*73") (pin "1") (pintype "passive"))
      (node (ref "*74") (pin "2") (pintype "passive"))
    )
    (net (code "81") (name "Net-(*75-Pad2)") (class "Default")
      (node (ref "*75") (pin "2") (pintype "passive"))
      (node (ref "*76") (pin "1") (pintype "passive"))
    )
    (net (code "82") (name "Net-(*77-Pad1)") (class "Default")
      (node (ref "*77") (pin "1") (pintype "passive"))
      (node (ref "*78") (pin "2") (pintype "passive"))
    )
    (net (code "83") (name "Net-(*79-Pad2)") (class "Default")
      (node (ref "*79") (pin "2") (pintype "passive"))
      (node (ref "*80") (pin "1") (pintype "passive"))
    )
    (net (code "84") (name "Net-(3-Pad1)") (class "Default")
      (node (ref "3") (pin "1") (pintype "passive"))
      (node (ref "4") (pin "1") (pintype "passive"))
    )
    (net (code "85") (name "Net-(5-Pad1)") (class "Default")
      (node (ref "5") (pin "1") (pintype "passive"))
      (node (ref "6") (pin "1") (pintype "passive"))
    )
    (net (code "86") (name "Net-(89-Pad2)") (class "Default")
      (node (ref "89") (pin "2") (pintype "passive"))
      (node (ref "pp9") (pin "4") (pinfunction "4_4") (pintype "passive"))
    )
    (net (code "87") (name "VCC") (class "Default")
      (node (ref "*") (pin "13") (pinfunction "13_13") (pintype "passive"))
      (node (ref "*") (pin "17") (pinfunction "17_17") (pintype "passive"))
      (node (ref "*1") (pin "17") (pinfunction "3.3V_17") (pintype "passive"))
      (node (ref "*1") (pin "33") (pinfunction "3.3V_33") (pintype "passive"))
      (node (ref "*1") (pin "50") (pinfunction "3.3v_50") (pintype "passive"))
      (node (ref "*15") (pin "7") (pinfunction "V+_7") (pintype "passive"))
      (node (ref "*5") (pin "7") (pinfunction "V+_7") (pintype "passive"))
      (node (ref "*7") (pin "1") (pintype "passive"))
      (node (ref "*9") (pin "7") (pinfunction "V+_7") (pintype "passive"))
      (node (ref "10") (pin "1") (pintype "passive"))
      (node (ref "11") (pin "1") (pintype "passive"))
      (node (ref "12") (pin "1") (pintype "passive"))
      (node (ref "13") (pin "1") (pintype "passive"))
      (node (ref "14") (pin "1") (pintype "passive"))
      (node (ref "15") (pin "1") (pintype "passive"))
      (node (ref "16") (pin "1") (pintype "passive"))
      (node (ref "17") (pin "1") (pintype "passive"))
      (node (ref "18") (pin "1") (pintype "passive"))
      (node (ref "19") (pin "1") (pintype "passive"))
      (node (ref "20") (pin "1") (pintype "passive"))
      (node (ref "21") (pin "1") (pintype "passive"))
      (node (ref "22") (pin "1") (pintype "passive"))
      (node (ref "23") (pin "1") (pintype "passive"))
      (node (ref "24") (pin "1") (pintype "passive"))
      (node (ref "25") (pin "1") (pintype "passive"))
      (node (ref "26") (pin "1") (pintype "passive"))
      (node (ref "27") (pin "1") (pintype "passive"))
      (node (ref "28") (pin "1") (pintype "passive"))
      (node (ref "29") (pin "1") (pintype "passive"))
      (node (ref "30") (pin "1") (pintype "passive"))
      (node (ref "31") (pin "1") (pintype "passive"))
      (node (ref "32") (pin "1") (pintype "passive"))
      (node (ref "33") (pin "1") (pintype "passive"))
      (node (ref "34") (pin "1") (pintype "passive"))
      (node (ref "35") (pin "1") (pintype "passive"))
      (node (ref "7") (pin "1") (pintype "passive"))
      (node (ref "8") (pin "1") (pintype "passive"))
      (node (ref "9") (pin "1") (pintype "passive"))
      (node (ref "VR") (pin "1") (pinfunction "Vin_1") (pintype "passive"))
      (node (ref "pp9") (pin "2") (pinfunction "2_2") (pintype "passive"))
      (node (ref "pp9") (pin "3") (pinfunction "3_3") (pintype "passive"))
    )
    (net (code "88") (name "VCC5") (class "Default")
      (node (ref "*1") (pin "66") (pinfunction "5V_66") (pintype "passive"))
      (node (ref "*1") (pin "67") (pinfunction "5V_67") (pintype "passive"))
      (node (ref "VR") (pin "3") (pinfunction "Vout_3") (pintype "passive"))
    )
    (net (code "89") (name "unconnected-(*-Pad1)") (class "Default")
      (node (ref "*") (pin "1") (pinfunction "1_1") (pintype "passive"))
    )
    (net (code "90") (name "unconnected-(*-Pad14)") (class "Default")
      (node (ref "*") (pin "14") (pinfunction "14_14") (pintype "passive"))
    )
    (net (code "91") (name "unconnected-(*-Pad15)") (class "Default")
      (node (ref "*") (pin "15") (pinfunction "15_15") (pintype "passive"))
    )
    (net (code "92") (name "unconnected-(*-Pad20)") (class "Default")
      (node (ref "*") (pin "20") (pinfunction "20_20") (pintype "passive"))
    )
    (net (code "93") (name "unconnected-(*-Pad21)") (class "Default")
      (node (ref "*") (pin "21") (pinfunction "21_21") (pintype "passive"))
    )
    (net (code "94") (name "unconnected-(*-Pad22)") (class "Default")
      (node (ref "*") (pin "22") (pinfunction "22_22") (pintype "passive"))
    )
    (net (code "95") (name "unconnected-(*-Pad23)") (class "Default")
      (node (ref "*") (pin "23") (pinfunction "23_23") (pintype "passive"))
    )
    (net (code "96") (name "unconnected-(*1-3.3V-Pad83)") (class "Default")
      (node (ref "*1") (pin "83") (pinfunction "3.3V_83") (pintype "passive"))
    )
    (net (code "97") (name "unconnected-(*1-3.3V-Pad116)") (class "Default")
      (node (ref "*1") (pin "116") (pinfunction "3.3V_116") (pintype "passive"))
    )
    (net (code "98") (name "unconnected-(*1-BOOT0-Pad70)") (class "Default")
      (node (ref "*1") (pin "70") (pinfunction "BOOT0_70") (pintype "passive"))
    )
    (net (code "99") (name "unconnected-(*1-PA0-Pad52)") (class "Default")
      (node (ref "*1") (pin "52") (pinfunction "PA0_52") (pintype "passive"))
    )
    (net (code "100") (name "unconnected-(*1-PA2-Pad51)") (class "Default")
      (node (ref "*1") (pin "51") (pinfunction "PA2_51") (pintype "passive"))
    )
    (net (code "101") (name "unconnected-(*1-PA3-Pad19)") (class "Default")
      (node (ref "*1") (pin "19") (pinfunction "PA3_19") (pintype "passive"))
    )
    (net (code "102") (name "unconnected-(*1-PA5-Pad20)") (class "Default")
      (node (ref "*1") (pin "20") (pinfunction "PA5_20") (pintype "passive"))
    )
    (net (code "103") (name "unconnected-(*1-PA6-Pad47)") (class "Default")
      (node (ref "*1") (pin "47") (pinfunction "PA6_47") (pintype "passive"))
    )
    (net (code "104") (name "unconnected-(*1-PA7-Pad21)") (class "Default")
      (node (ref "*1") (pin "21") (pinfunction "PA7_21") (pintype "passive"))
    )
    (net (code "105") (name "unconnected-(*1-PA8-Pad87)") (class "Default")
      (node (ref "*1") (pin "87") (pinfunction "PA8_87") (pintype "passive"))
    )
    (net (code "106") (name "unconnected-(*1-PA9-Pad112)") (class "Default")
      (node (ref "*1") (pin "112") (pinfunction "PA9_112") (pintype "passive"))
    )
    (net (code "107") (name "unconnected-(*1-PA10-Pad86)") (class "Default")
      (node (ref "*1") (pin "86") (pinfunction "PA10_86") (pintype "passive"))
    )
    (net (code "108") (name "unconnected-(*1-PA11-Pad113)") (class "Default")
      (node (ref "*1") (pin "113") (pinfunction "PA11_113") (pintype "passive"))
    )
    (net (code "109") (name "unconnected-(*1-PA12-Pad85)") (class "Default")
      (node (ref "*1") (pin "85") (pinfunction "PA12_85") (pintype "passive"))
    )
    (net (code "110") (name "unconnected-(*1-PA13-Pad114)") (class "Default")
      (node (ref "*1") (pin "114") (pinfunction "PA13_114") (pintype "passive"))
    )
    (net (code "111") (name "unconnected-(*1-PA14-Pad117)") (class "Default")
      (node (ref "*1") (pin "117") (pinfunction "PA14_117") (pintype "passive"))
    )
    (net (code "112") (name "unconnected-(*1-PA15-Pad82)") (class "Default")
      (node (ref "*1") (pin "82") (pinfunction "PA15_82") (pintype "passive"))
    )
    (net (code "113") (name "unconnected-(*1-PB0-Pad45)") (class "Default")
      (node (ref "*1") (pin "45") (pinfunction "PB0_45") (pintype "passive"))
    )
    (net (code "114") (name "unconnected-(*1-PB1-Pad23)") (class "Default")
      (node (ref "*1") (pin "23") (pinfunction "PB1_23") (pintype "passive"))
    )
    (net (code "115") (name "unconnected-(*1-PB2-Pad44)") (class "Default")
      (node (ref "*1") (pin "44") (pinfunction "PB2_44") (pintype "passive"))
    )
    (net (code "116") (name "unconnected-(*1-PB3-Pad127)") (class "Default")
      (node (ref "*1") (pin "127") (pinfunction "PB3_127") (pintype "passive"))
    )
    (net (code "117") (name "unconnected-(*1-PB4-Pad72)") (class "Default")
      (node (ref "*1") (pin "72") (pinfunction "PB4_72") (pintype "passive"))
    )
    (net (code "118") (name "unconnected-(*1-PB5-Pad128)") (class "Default")
      (node (ref "*1") (pin "128") (pinfunction "PB5_128") (pintype "passive"))
    )
    (net (code "119") (name "unconnected-(*1-PB6-Pad71)") (class "Default")
      (node (ref "*1") (pin "71") (pinfunction "PB6_71") (pintype "passive"))
    )
    (net (code "120") (name "unconnected-(*1-PB8-Pad130)") (class "Default")
      (node (ref "*1") (pin "130") (pinfunction "PB8_130") (pintype "passive"))
    )
    (net (code "121") (name "unconnected-(*1-PB9-Pad69)") (class "Default")
      (node (ref "*1") (pin "69") (pinfunction "PB9_69") (pintype "passive"))
    )
    (net (code "122") (name "unconnected-(*1-PB10-Pad32)") (class "Default")
      (node (ref "*1") (pin "32") (pinfunction "PB10_32") (pintype "passive"))
    )
    (net (code "123") (name "unconnected-(*1-PB11-Pad35)") (class "Default")
      (node (ref "*1") (pin "35") (pinfunction "PB11_35") (pintype "passive"))
    )
    (net (code "124") (name "unconnected-(*1-PB12-Pad100)") (class "Default")
      (node (ref "*1") (pin "100") (pinfunction "PB12_100") (pintype "passive"))
    )
    (net (code "125") (name "unconnected-(*1-PB13-Pad98)") (class "Default")
      (node (ref "*1") (pin "98") (pinfunction "PB13_98") (pintype "passive"))
    )
    (net (code "126") (name "unconnected-(*1-PB14-Pad101)") (class "Default")
      (node (ref "*1") (pin "101") (pinfunction "PB14_101") (pintype "passive"))
    )
    (net (code "127") (name "unconnected-(*1-PB15-Pad97)") (class "Default")
      (node (ref "*1") (pin "97") (pinfunction "PB15_97") (pintype "passive"))
    )
    (net (code "128") (name "unconnected-(*1-PC0-Pad54)") (class "Default")
      (node (ref "*1") (pin "54") (pinfunction "PC0_54") (pintype "passive"))
    )
    (net (code "129") (name "unconnected-(*1-PC1-Pad14)") (class "Default")
      (node (ref "*1") (pin "14") (pinfunction "PC1_14") (pintype "passive"))
    )
    (net (code "130") (name "unconnected-(*1-PC2-Pad53)") (class "Default")
      (node (ref "*1") (pin "53") (pinfunction "PC2_53") (pintype "passive"))
    )
    (net (code "131") (name "unconnected-(*1-PC3-Pad15)") (class "Default")
      (node (ref "*1") (pin "15") (pinfunction "PC3_15") (pintype "passive"))
    )
    (net (code "132") (name "unconnected-(*1-PC6-Pad89)") (class "Default")
      (node (ref "*1") (pin "89") (pinfunction "PC6_89") (pintype "passive"))
    )
    (net (code "133") (name "unconnected-(*1-PC7-Pad110)") (class "Default")
      (node (ref "*1") (pin "110") (pinfunction "PC7_110") (pintype "passive"))
    )
    (net (code "134") (name "unconnected-(*1-PC8-Pad88)") (class "Default")
      (node (ref "*1") (pin "88") (pinfunction "PC8_88") (pintype "passive"))
    )
    (net (code "135") (name "unconnected-(*1-PC9-Pad111)") (class "Default")
      (node (ref "*1") (pin "111") (pinfunction "PC9_111") (pintype "passive"))
    )
    (net (code "136") (name "unconnected-(*1-PC10-Pad118)") (class "Default")
      (node (ref "*1") (pin "118") (pinfunction "PC10_118") (pintype "passive"))
    )
    (net (code "137") (name "unconnected-(*1-PC11-Pad81)") (class "Default")
      (node (ref "*1") (pin "81") (pinfunction "PC11_81") (pintype "passive"))
    )
    (net (code "138") (name "unconnected-(*1-PC12-Pad119)") (class "Default")
      (node (ref "*1") (pin "119") (pinfunction "PC12_119") (pintype "passive"))
    )
    (net (code "139") (name "unconnected-(*1-PC13-Pad5)") (class "Default")
      (node (ref "*1") (pin "5") (pinfunction "PC13_5") (pintype "passive"))
    )
    (net (code "140") (name "unconnected-(*1-PC14-Pad62)") (class "Default")
      (node (ref "*1") (pin "62") (pinfunction "PC14_62") (pintype "passive"))
    )
    (net (code "141") (name "unconnected-(*1-PC15-Pad6)") (class "Default")
      (node (ref "*1") (pin "6") (pinfunction "PC15_6") (pintype "passive"))
    )
    (net (code "142") (name "unconnected-(*1-PD2-Pad79)") (class "Default")
      (node (ref "*1") (pin "79") (pinfunction "PD2_79") (pintype "passive"))
    )
    (net (code "143") (name "unconnected-(*1-PD6-Pad77)") (class "Default")
      (node (ref "*1") (pin "77") (pinfunction "PD6_77") (pintype "passive"))
    )
    (net (code "144") (name "unconnected-(*1-PD11-Pad95)") (class "Default")
      (node (ref "*1") (pin "95") (pinfunction "PD11_95") (pintype "passive"))
    )
    (net (code "145") (name "unconnected-(*1-PD12-Pad104)") (class "Default")
      (node (ref "*1") (pin "104") (pinfunction "PD12_104") (pintype "passive"))
    )
    (net (code "146") (name "unconnected-(*1-PE0-Pad131)") (class "Default")
      (node (ref "*1") (pin "131") (pinfunction "PE0_131") (pintype "passive"))
    )
    (net (code "147") (name "unconnected-(*1-PE1-Pad68)") (class "Default")
      (node (ref "*1") (pin "68") (pinfunction "PE1_68") (pintype "passive"))
    )
    (net (code "148") (name "unconnected-(*1-PE2-Pad2)") (class "Default")
      (node (ref "*1") (pin "2") (pinfunction "PE2_2") (pintype "passive"))
    )
    (net (code "149") (name "unconnected-(*1-PE3-Pad65)") (class "Default")
      (node (ref "*1") (pin "65") (pinfunction "PE3_65") (pintype "passive"))
    )
    (net (code "150") (name "unconnected-(*1-PE4-Pad3)") (class "Default")
      (node (ref "*1") (pin "3") (pinfunction "PE4_3") (pintype "passive"))
    )
    (net (code "151") (name "unconnected-(*1-PE5-Pad64)") (class "Default")
      (node (ref "*1") (pin "64") (pinfunction "PE5_64") (pintype "passive"))
    )
    (net (code "152") (name "unconnected-(*1-PE6-Pad4)") (class "Default")
      (node (ref "*1") (pin "4") (pinfunction "PE6_4") (pintype "passive"))
    )
    (net (code "153") (name "unconnected-(*1-PF6-Pad58)") (class "Default")
      (node (ref "*1") (pin "58") (pinfunction "PF6_58") (pintype "passive"))
    )
    (net (code "154") (name "unconnected-(*1-PF7-Pad10)") (class "Default")
      (node (ref "*1") (pin "10") (pinfunction "PF7_10") (pintype "passive"))
    )
    (net (code "155") (name "unconnected-(*1-PF8-Pad57)") (class "Default")
      (node (ref "*1") (pin "57") (pinfunction "PF8_57") (pintype "passive"))
    )
    (net (code "156") (name "unconnected-(*1-PF9-Pad11)") (class "Default")
      (node (ref "*1") (pin "11") (pinfunction "PF9_11") (pintype "passive"))
    )
    (net (code "157") (name "unconnected-(*1-PF10-Pad56)") (class "Default")
      (node (ref "*1") (pin "56") (pinfunction "PF10_56") (pintype "passive"))
    )
    (net (code "158") (name "unconnected-(*1-PF11-Pad24)") (class "Default")
      (node (ref "*1") (pin "24") (pinfunction "PF11_24") (pintype "passive"))
    )
    (net (code "159") (name "unconnected-(*1-PG0-Pad41)") (class "Default")
      (node (ref "*1") (pin "41") (pinfunction "PG0_41") (pintype "passive"))
    )
    (net (code "160") (name "unconnected-(*1-PG1-Pad27)") (class "Default")
      (node (ref "*1") (pin "27") (pinfunction "PG1_27") (pintype "passive"))
    )
    (net (code "161") (name "unconnected-(*1-PG2-Pad106)") (class "Default")
      (node (ref "*1") (pin "106") (pinfunction "PG2_106") (pintype "passive"))
    )
    (net (code "162") (name "unconnected-(*1-PG3-Pad92)") (class "Default")
      (node (ref "*1") (pin "92") (pinfunction "PG3_92") (pintype "passive"))
    )
    (net (code "163") (name "unconnected-(*1-PG4-Pad107)") (class "Default")
      (node (ref "*1") (pin "107") (pinfunction "PG4_107") (pintype "passive"))
    )
    (net (code "164") (name "unconnected-(*1-PG5-Pad91)") (class "Default")
      (node (ref "*1") (pin "91") (pinfunction "PG5_91") (pintype "passive"))
    )
    (net (code "165") (name "unconnected-(*1-PG6-Pad108)") (class "Default")
      (node (ref "*1") (pin "108") (pinfunction "PG6_108") (pintype "passive"))
    )
    (net (code "166") (name "unconnected-(*1-PG7-Pad90)") (class "Default")
      (node (ref "*1") (pin "90") (pinfunction "PG7_90") (pintype "passive"))
    )
    (net (code "167") (name "unconnected-(*1-PG8-Pad109)") (class "Default")
      (node (ref "*1") (pin "109") (pinfunction "PG8_109") (pintype "passive"))
    )
    (net (code "168") (name "unconnected-(*1-PG9-Pad76)") (class "Default")
      (node (ref "*1") (pin "76") (pinfunction "PG9_76") (pintype "passive"))
    )
    (net (code "169") (name "unconnected-(*1-PG10-Pad124)") (class "Default")
      (node (ref "*1") (pin "124") (pinfunction "PG10_124") (pintype "passive"))
    )
    (net (code "170") (name "unconnected-(*1-PG11-Pad75)") (class "Default")
      (node (ref "*1") (pin "75") (pinfunction "PG11_75") (pintype "passive"))
    )
    (net (code "171") (name "unconnected-(*1-PG12-Pad125)") (class "Default")
      (node (ref "*1") (pin "125") (pinfunction "PG12_125") (pintype "passive"))
    )
    (net (code "172") (name "unconnected-(*1-PG13-Pad74)") (class "Default")
      (node (ref "*1") (pin "74") (pinfunction "PG13_74") (pintype "passive"))
    )
    (net (code "173") (name "unconnected-(*1-PG14-Pad126)") (class "Default")
      (node (ref "*1") (pin "126") (pinfunction "PG14_126") (pintype "passive"))
    )
    (net (code "174") (name "unconnected-(*1-PG15-Pad73)") (class "Default")
      (node (ref "*1") (pin "73") (pinfunction "PG15_73") (pintype "passive"))
    )
    (net (code "175") (name "unconnected-(*1-PH0-Pad12)") (class "Default")
      (node (ref "*1") (pin "12") (pinfunction "PH0_12") (pintype "passive"))
    )
    (net (code "176") (name "unconnected-(*1-PH1-Pad55)") (class "Default")
      (node (ref "*1") (pin "55") (pinfunction "PH1_55") (pintype "passive"))
    )
    (net (code "177") (name "unconnected-(*1-VBAT-Pad63)") (class "Default")
      (node (ref "*1") (pin "63") (pinfunction "VBAT_63") (pintype "passive"))
    )
    (net (code "178") (name "unconnected-(*5-NC-Pad1)") (class "Default")
      (node (ref "*5") (pin "1") (pinfunction "NC_1") (pintype "passive+no_connect"))
    )
    (net (code "179") (name "unconnected-(*5-NC-Pad5)") (class "Default")
      (node (ref "*5") (pin "5") (pinfunction "NC_5") (pintype "passive+no_connect"))
    )
    (net (code "180") (name "unconnected-(*5-NC-Pad8)") (class "Default")
      (node (ref "*5") (pin "8") (pinfunction "NC_8") (pintype "passive+no_connect"))
    )
    (net (code "181") (name "unconnected-(*9-NC-Pad1)") (class "Default")
      (node (ref "*9") (pin "1") (pinfunction "NC_1") (pintype "passive+no_connect"))
    )
    (net (code "182") (name "unconnected-(*9-NC-Pad5)") (class "Default")
      (node (ref "*9") (pin "5") (pinfunction "NC_5") (pintype "passive+no_connect"))
    )
    (net (code "183") (name "unconnected-(*9-NC-Pad8)") (class "Default")
      (node (ref "*9") (pin "8") (pinfunction "NC_8") (pintype "passive+no_connect"))
    )
    (net (code "184") (name "unconnected-(*15-NC-Pad1)") (class "Default")
      (node (ref "*15") (pin "1") (pinfunction "NC_1") (pintype "passive+no_connect"))
    )
    (net (code "185") (name "unconnected-(*15-NC-Pad5)") (class "Default")
      (node (ref "*15") (pin "5") (pinfunction "NC_5") (pintype "passive+no_connect"))
    )
    (net (code "186") (name "unconnected-(*15-NC-Pad8)") (class "Default")
      (node (ref "*15") (pin "8") (pinfunction "NC_8") (pintype "passive+no_connect"))
    )
    (net (code "187") (name "unconnected-(pp9-Pad5)") (class "Default")
      (node (ref "pp9") (pin "5") (pinfunction "5_5") (pintype "passive+no_connect"))
    )
  )
)
